# YA-S-Radio-V1_0.net
KiCad netlist of a schematic drawn in Altium Designer
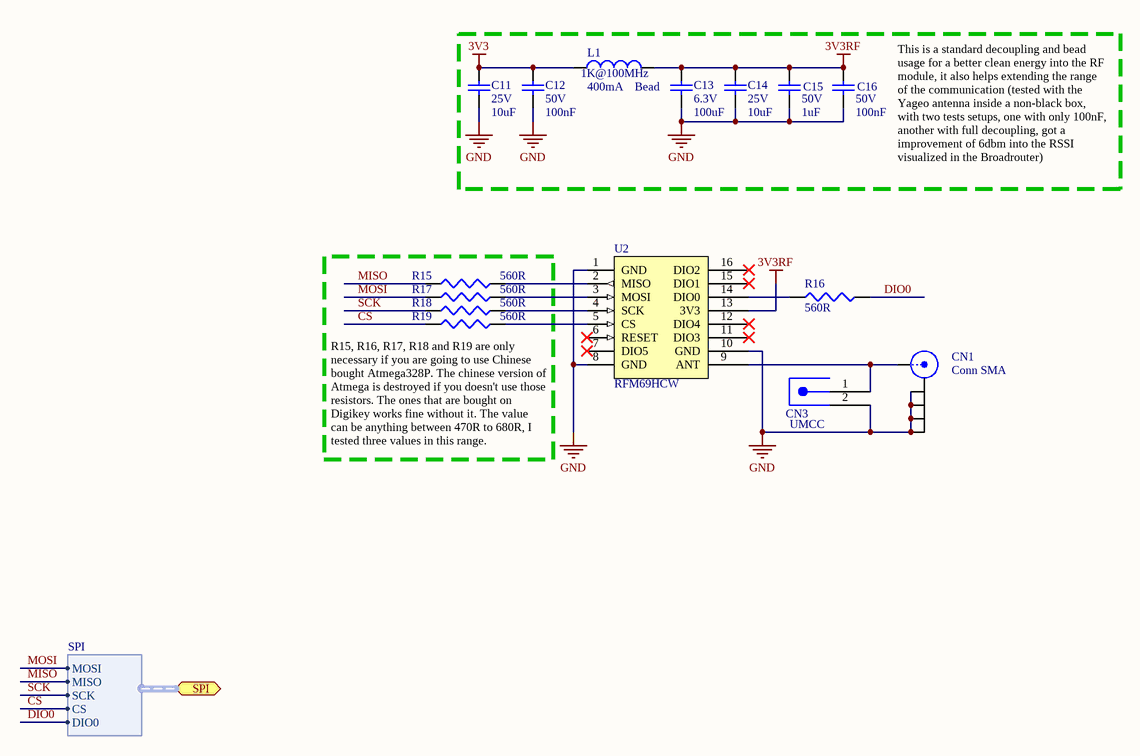
[diagram p0: YA-S-Radio-V1.0.SchDoc]

(export (version "E")
  (design (tool "Eeschema 10.0.6"))
  (components
    (comp (ref "C11")
      (value "10uF")
      (footprint "CC0805")
      (description "Capacitor (Semiconductor SIM Model)")
      (fields (field (name "TENSÃO") "25V") (field (name "Comment") "Capacitor Cerâmico"))
      (libsource (lib "NavarroCAP") (part "Cap 10uF 25V 0805 X5R"))
    )
    (comp (ref "C12")
      (value "100nF")
      (footprint "CC0603")
      (description "Capacitor (Semiconductor SIM Model)")
      (fields (field (name "TENSÃO") "50V") (field (name "Comment") "Capacitor Cerâmico"))
      (libsource (lib "NavarroCAP") (part "Cap 100nF 50V 0603 X7R"))
    )
    (comp (ref "C13")
      (value "100uF")
      (footprint "CC1206")
      (description "Capacitor (Semiconductor SIM Model)")
      (fields (field (name "TENSÃO") "6.3V") (field (name "Comment") "Capacitor Cerâmico"))
      (libsource (lib "NavarroCAP") (part "Cap 100uF 6.3V 1206 X5R"))
    )
    (comp (ref "C14")
      (value "10uF")
      (footprint "CC0805")
      (description "Capacitor (Semiconductor SIM Model)")
      (fields (field (name "TENSÃO") "25V") (field (name "Comment") "Capacitor Cerâmico"))
      (libsource (lib "NavarroCAP") (part "Cap 10uF 25V 0805 X5R"))
    )
    (comp (ref "C15")
      (value "1uF")
      (footprint "CC0603")
      (description "Capacitor (Semiconductor SIM Model)")
      (fields (field (name "TENSÃO") "50V") (field (name "Comment") "Capacitor Cerâmico"))
      (libsource (lib "NavarroCAP") (part "Cap 1uF 50V 0603 X5R"))
    )
    (comp (ref "C16")
      (value "100nF")
      (footprint "CC0603")
      (description "Capacitor (Semiconductor SIM Model)")
      (fields (field (name "TENSÃO") "50V") (field (name "Comment") "Capacitor Cerâmico"))
      (libsource (lib "NavarroCAP") (part "Cap 100nF 50V 0603 X7R"))
    )
    (comp (ref "CN1")
      (value "Conn SMA")
      (footprint "CONN SMA-JACK")
      (description "Conector SMA")
      (libsource (lib "NavarroCON") (part "Conn SMA"))
    )
    (comp (ref "CN3")
      (value "UMCC")
      (footprint "CONN U.FL")
      (libsource (lib "NavarroCON") (part "Conn UMCC TE"))
    )
    (comp (ref "L1")
      (value "Bead")
      (footprint "CC0603")
      (fields (field (name "CORRENTE") "400mA") (field (name "ALTIUM_VALUE") "1K@100MHz"))
      (libsource (lib "NavarroIND") (part "Bd 1K@100MHz 0603 400mA"))
    )
    (comp (ref "R15")
      (value "560R")
      (footprint "CC0603")
      (description "Resistor")
      (libsource (lib "NavarroRES") (part "Res 560R 1% 0603 1/10w"))
    )
    (comp (ref "R16")
      (value "560R")
      (footprint "CC0603")
      (description "Resistor")
      (libsource (lib "NavarroRES") (part "Res 560R 1% 0603 1/10w"))
    )
    (comp (ref "R17")
      (value "560R")
      (footprint "CC0603")
      (description "Resistor")
      (libsource (lib "NavarroRES") (part "Res 560R 1% 0603 1/10w"))
    )
    (comp (ref "R18")
      (value "560R")
      (footprint "CC0603")
      (description "Resistor")
      (libsource (lib "NavarroRES") (part "Res 560R 1% 0603 1/10w"))
    )
    (comp (ref "R19")
      (value "560R")
      (footprint "CC0603")
      (description "Resistor")
      (libsource (lib "NavarroRES") (part "Res 560R 1% 0603 1/10w"))
    )
    (comp (ref "U2")
      (value "RFM69HCW")
      (footprint "RFM69HCW")
      (description "Memória")
      (libsource (lib "Navarro") (part "RFM69HCW"))
    )
  )
  (nets
    (net (code "2") (name "/CS") (class "Default")
      (node (ref "R19") (pin "1") (pinfunction "1_1") (pintype "passive"))
    )
    (net (code "3") (name "/DIO0") (class "Default")
      (node (ref "R16") (pin "2") (pinfunction "2_2") (pintype "passive"))
    )
    (net (code "4") (name "/MISO") (class "Default")
      (node (ref "R15") (pin "1") (pinfunction "1_1") (pintype "passive"))
    )
    (net (code "5") (name "/MOSI") (class "Default")
      (node (ref "R17") (pin "1") (pinfunction "1_1") (pintype "passive"))
    )
    (net (code "6") (name "/SCK") (class "Default")
      (node (ref "R18") (pin "1") (pinfunction "1_1") (pintype "passive"))
    )
    (net (code "8") (name "3V3") (class "Default")
      (node (ref "C11") (pin "2") (pinfunction "2_2") (pintype "passive"))
      (node (ref "C12") (pin "2") (pinfunction "2_2") (pintype "passive"))
      (node (ref "L1") (pin "1") (pinfunction "1_1") (pintype "passive"))
    )
    (net (code "9") (name "3V3RF") (class "Default")
      (node (ref "C13") (pin "2") (pinfunction "2_2") (pintype "passive"))
      (node (ref "C14") (pin "2") (pinfunction "2_2") (pintype "passive"))
      (node (ref "C15") (pin "2") (pinfunction "2_2") (pintype "passive"))
      (node (ref "C16") (pin "2") (pinfunction "2_2") (pintype "passive"))
      (node (ref "L1") (pin "2") (pinfunction "2_2") (pintype "passive"))
      (node (ref "U2") (pin "13") (pinfunction "3V3_13") (pintype "power_in"))
    )
    (net (code "10") (name "GND") (class "Default")
      (node (ref "C11") (pin "1") (pinfunction "1_1") (pintype "passive"))
      (node (ref "C12") (pin "1") (pinfunction "1_1") (pintype "passive"))
      (node (ref "C13") (pin "1") (pinfunction "1_1") (pintype "passive"))
      (node (ref "C14") (pin "1") (pinfunction "1_1") (pintype "passive"))
      (node (ref "C15") (pin "1") (pinfunction "1_1") (pintype "passive"))
      (node (ref "C16") (pin "1") (pinfunction "1_1") (pintype "passive"))
      (node (ref "CN1") (pin "2") (pinfunction "Y_2") (pintype "passive"))
      (node (ref "CN1") (pin "3") (pinfunction "Y_3") (pintype "passive"))
      (node (ref "CN1") (pin "4") (pinfunction "Y_4") (pintype "passive"))
      (node (ref "CN1") (pin "5") (pinfunction "Y_5") (pintype "passive"))
      (node (ref "CN3") (pin "2") (pinfunction "2_2") (pintype "passive"))
      (node (ref "U2") (pin "1") (pinfunction "GND_1") (pintype "power_in"))
      (node (ref "U2") (pin "10") (pinfunction "GND_10") (pintype "power_in"))
      (node (ref "U2") (pin "8") (pinfunction "GND_8") (pintype "power_in"))
    )
    (net (code "11") (name "Net-(CN1-X)") (class "Default")
      (node (ref "CN1") (pin "1") (pinfunction "X_1") (pintype "passive"))
      (node (ref "CN3") (pin "1") (pinfunction "1_1") (pintype "passive"))
      (node (ref "U2") (pin "9") (pinfunction "ANT_9") (pintype "passive"))
    )
    (net (code "12") (name "Net-(U2-CS)") (class "Default")
      (node (ref "R19") (pin "2") (pinfunction "2_2") (pintype "passive"))
      (node (ref "U2") (pin "5") (pinfunction "CS_5") (pintype "input"))
    )
    (net (code "13") (name "Net-(U2-DIO0)") (class "Default")
      (node (ref "R16") (pin "1") (pinfunction "1_1") (pintype "passive"))
      (node (ref "U2") (pin "14") (pinfunction "DIO0_14") (pintype "passive"))
    )
    (net (code "14") (name "Net-(U2-MISO)") (class "Default")
      (node (ref "R15") (pin "2") (pinfunction "2_2") (pintype "passive"))
      (node (ref "U2") (pin "2") (pinfunction "MISO_2") (pintype "output"))
    )
    (net (code "15") (name "Net-(U2-MOSI)") (class "Default")
      (node (ref "R17") (pin "2") (pinfunction "2_2") (pintype "passive"))
      (node (ref "U2") (pin "3") (pinfunction "MOSI_3") (pintype "input"))
    )
    (net (code "16") (name "Net-(U2-SCK)") (class "Default")
      (node (ref "R18") (pin "2") (pinfunction "2_2") (pintype "passive"))
      (node (ref "U2") (pin "4") (pinfunction "SCK_4") (pintype "input"))
    )
    (net (code "17") (name "unconnected-(U2-DIO1-Pad15)") (class "Default")
      (node (ref "U2") (pin "15") (pinfunction "DIO1_15") (pintype "passive+no_connect"))
    )
    (net (code "18") (name "unconnected-(U2-DIO2-Pad16)") (class "Default")
      (node (ref "U2") (pin "16") (pinfunction "DIO2_16") (pintype "passive+no_connect"))
    )
    (net (code "19") (name "unconnected-(U2-DIO3-Pad11)") (class "Default")
      (node (ref "U2") (pin "11") (pinfunction "DIO3_11") (pintype "passive+no_connect"))
    )
    (net (code "20") (name "unconnected-(U2-DIO4-Pad12)") (class "Default")
      (node (ref "U2") (pin "12") (pinfunction "DIO4_12") (pintype "passive+no_connect"))
    )
    (net (code "21") (name "unconnected-(U2-DIO5-Pad7)") (class "Default")
      (node (ref "U2") (pin "7") (pinfunction "DIO5_7") (pintype "passive+no_connect"))
    )
    (net (code "22") (name "unconnected-(U2-RESET-Pad6)") (class "Default")
      (node (ref "U2") (pin "6") (pinfunction "RESET_6") (pintype "input+no_connect"))
    )
  )
)
